# sender.net
KiCad netlist of a schematic drawn in EAGLE
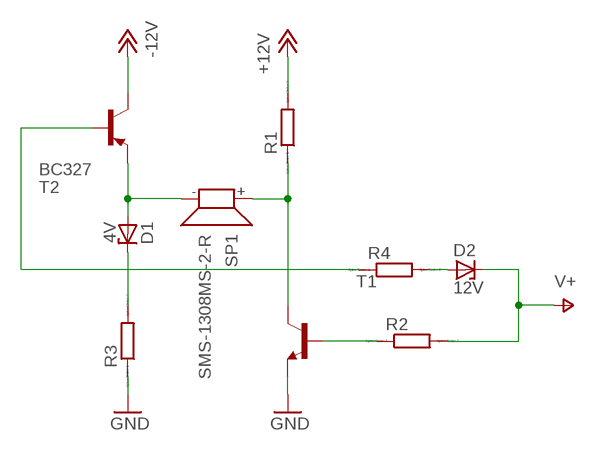
[diagram p0: schematic, sheet 1]

(export (version "E")
  (design (tool "Eeschema 10.0.6"))
  (components
    (comp (ref "D1")
      (value "4V")
      (footprint "eagle-import:C1702-15")
      (libsource (lib "eagle-import") (part "ZENER-DIODEC1702-15"))
    )
    (comp (ref "D2")
      (value "12V")
      (footprint "eagle-import:C1702-15")
      (libsource (lib "eagle-import") (part "ZENER-DIODEC1702-15"))
    )
    (comp (ref "R1")
      (value "R-EU_0204_7")
      (footprint "eagle-import:0204_7")
      (libsource (lib "eagle-import") (part "R-EU_0204_7"))
    )
    (comp (ref "R2")
      (value "R-EU_0204_7")
      (footprint "eagle-import:0204_7")
      (libsource (lib "eagle-import") (part "R-EU_0204_7"))
    )
    (comp (ref "R3")
      (value "R-EU_0204_7")
      (footprint "eagle-import:0204_7")
      (libsource (lib "eagle-import") (part "R-EU_0204_7"))
    )
    (comp (ref "R4")
      (value "R-EU_0204_7")
      (footprint "eagle-import:0204_7")
      (libsource (lib "eagle-import") (part "R-EU_0204_7"))
    )
    (comp (ref "SP1")
      (value "SMS-1308MS-2-R")
      (footprint "eagle-import:SMS-1308MS-2-R")
      (libsource (lib "eagle-import") (part "SMS-1308MS-2-R"))
    )
    (comp (ref "T1")
      (value "-NPN-TO92L")
      (footprint "eagle-import:TO92L")
      (libsource (lib "eagle-import") (part "-NPN-TO92L"))
    )
    (comp (ref "T2")
      (value "BC327")
      (footprint "eagle-import:TO92")
      (libsource (lib "eagle-import") (part "BC327"))
    )
  )
  (nets
    (net (code "1") (name "+12V") (class "Default")
      (node (ref "R1") (pin "2") (pinfunction "2_2") (pintype "passive"))
    )
    (net (code "2") (name "-12V") (class "Default")
      (node (ref "T2") (pin "3") (pinfunction "C_3") (pintype "passive"))
    )
    (net (code "3") (name "GND") (class "Default")
      (node (ref "R3") (pin "1") (pinfunction "1_1") (pintype "passive"))
      (node (ref "T1") (pin "1") (pinfunction "E_1") (pintype "passive"))
    )
    (net (code "4") (name "Net-(D1-PadC)") (class "Default")
      (node (ref "D1") (pin "C") (pinfunction "C_C") (pintype "passive"))
      (node (ref "R3") (pin "2") (pinfunction "2_2") (pintype "passive"))
    )
    (net (code "5") (name "Net-(D2-PadA)") (class "Default")
      (node (ref "D2") (pin "A") (pinfunction "A_A") (pintype "passive"))
      (node (ref "R4") (pin "2") (pinfunction "2_2") (pintype "passive"))
    )
    (net (code "6") (name "Net-(SP1-1)") (class "Default")
      (node (ref "R1") (pin "1") (pinfunction "1_1") (pintype "passive"))
      (node (ref "SP1") (pin "+") (pinfunction "1_+") (pintype "passive"))
      (node (ref "T1") (pin "3") (pinfunction "C_3") (pintype "passive"))
    )
    (net (code "7") (name "Net-(SP1-2)") (class "Default")
      (node (ref "D1") (pin "A") (pinfunction "A_A") (pintype "passive"))
      (node (ref "SP1") (pin "-") (pinfunction "2_-") (pintype "passive"))
      (node (ref "T2") (pin "1") (pinfunction "E_1") (pintype "passive"))
    )
    (net (code "8") (name "Net-(T1-B)") (class "Default")
      (node (ref "R2") (pin "1") (pinfunction "1_1") (pintype "passive"))
      (node (ref "T1") (pin "2") (pinfunction "B_2") (pintype "passive"))
    )
    (net (code "9") (name "Net-(T2-B)") (class "Default")
      (node (ref "R4") (pin "1") (pinfunction "1_1") (pintype "passive"))
      (node (ref "T2") (pin "2") (pinfunction "B_2") (pintype "passive"))
    )
    (net (code "10") (name "V+") (class "Default")
      (node (ref "D2") (pin "C") (pinfunction "C_C") (pintype "passive"))
      (node (ref "R2") (pin "2") (pinfunction "2_2") (pintype "passive"))
    )
  )
)
